# rtc_blk.net
KiCad netlist of a schematic drawn in Altium Designer
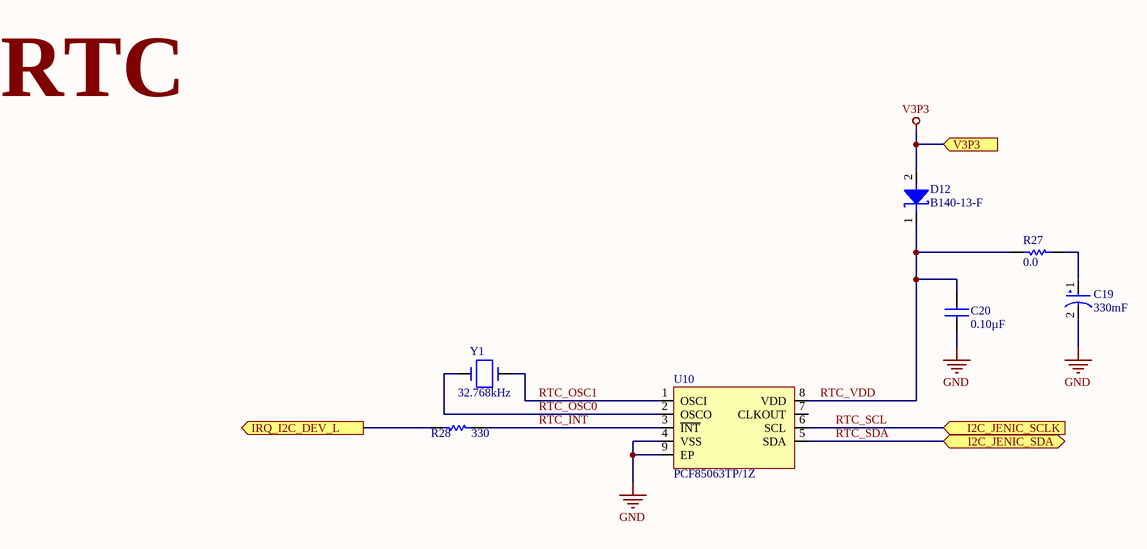
[diagram p0: rtc_blk.SchDoc]

(export (version "E")
  (design (tool "Eeschema 10.0.6"))
  (components
    (comp (ref "C19")
      (value "330mF")
      (footprint "ELNA_DSK-3R3H334T-HL")
      (description "CAP 330MF -20% +80% 3.3V SMD")
      (fields (field (name "MPN") "DSK-3R3H334T-HL"))
      (libsource (lib "Capacitor") (part "DSK-3R3H334T-HL"))
    )
    (comp (ref "C20")
      (value "0.10µF")
      (footprint "C0402")
      (description "CAP CER 0.1UF 50V X7R 0402")
      (fields (field (name "MPN") "GRM155R71H104ME14D"))
      (libsource (lib "Capacitor") (part "GRM155R71H104ME14D"))
    )
    (comp (ref "D12")
      (value "B140-13-F")
      (footprint "DO-214AC, SMA")
      (description "DIODE SCHOTTKY 40V 1A SMA")
      (libsource (lib "Diode") (part "B140-13-F"))
    )
    (comp (ref "R27")
      (value "0.0")
      (footprint "R0402")
      (description "RES SMD 0.0OHM JUMPER 1/16W 0402")
      (fields (field (name "MPN") "CRCW04020000Z0ED"))
      (libsource (lib "Res") (part "CRCW04020000Z0ED"))
    )
    (comp (ref "R28")
      (value "330")
      (footprint "R0402")
      (description "RES SMD 330 OHM 1% 1/16W 0402")
      (fields (field (name "MPN") "CRCW0402330RFKED"))
      (libsource (lib "Res") (part "CRCW0402330RFKED"))
    )
    (comp (ref "U10")
      (value "PCF85063TP/1Z")
      (footprint "SON9P50_200X300X80L40X24T150N")
      (description "Real Time Clock Serial 8-Pin HWSON EP")
      (fields (field (name "MPN") "PCF85063TP/1Z"))
      (libsource (lib "IC") (part "PCF85063TP/1Z"))
    )
    (comp (ref "Y1")
      (value "32.768kHz")
      (footprint "XTAL320X150X80L75X150N")
      (description "CRYSTAL 32.7680 KHZ 7.0PF SMD")
      (fields (field (name "MPN") "FC-13532.7680KA-AG5"))
      (libsource (lib "Crystal") (part "FC-13532.7680KA-AG5"))
    )
  )
  (nets
    (net (code "1") (name "/IRQ_I2C_DEV_L") (class "Default")
      (node (ref "R28") (pin "2") (pinfunction "2_2") (pintype "passive"))
    )
    (net (code "2") (name "/RTC_INT") (class "Default")
      (node (ref "R28") (pin "1") (pinfunction "1_1") (pintype "passive"))
      (node (ref "U10") (pin "3") (pinfunction "~{INT}_3") (pintype "passive"))
    )
    (net (code "3") (name "/RTC_OSC0") (class "Default")
      (node (ref "U10") (pin "2") (pinfunction "OSCO_2") (pintype "passive"))
      (node (ref "Y1") (pin "1") (pinfunction "1_1") (pintype "passive"))
    )
    (net (code "4") (name "/RTC_OSC1") (class "Default")
      (node (ref "U10") (pin "1") (pinfunction "OSCI_1") (pintype "passive"))
      (node (ref "Y1") (pin "2") (pinfunction "2_2") (pintype "passive"))
    )
    (net (code "5") (name "/RTC_SCL") (class "Default")
      (node (ref "U10") (pin "6") (pinfunction "SCL_6") (pintype "passive"))
    )
    (net (code "6") (name "/RTC_SDA") (class "Default")
      (node (ref "U10") (pin "5") (pinfunction "SDA_5") (pintype "passive"))
    )
    (net (code "7") (name "/RTC_VDD") (class "Default")
      (node (ref "C20") (pin "1") (pinfunction "1_1") (pintype "passive"))
      (node (ref "D12") (pin "1") (pinfunction "cathode_1") (pintype "passive"))
      (node (ref "R27") (pin "1") (pinfunction "1_1") (pintype "passive"))
      (node (ref "U10") (pin "8") (pinfunction "VDD_8") (pintype "passive"))
    )
    (net (code "8") (name "GND") (class "Default")
      (node (ref "C19") (pin "2") (pinfunction "2_2") (pintype "passive"))
      (node (ref "C20") (pin "2") (pinfunction "2_2") (pintype "passive"))
      (node (ref "U10") (pin "4") (pinfunction "VSS_4") (pintype "passive"))
      (node (ref "U10") (pin "9") (pinfunction "EP_9") (pintype "passive"))
    )
    (net (code "9") (name "Net-(C19-Pad1)") (class "Default")
      (node (ref "C19") (pin "1") (pinfunction "1_1") (pintype "passive"))
      (node (ref "R27") (pin "2") (pinfunction "2_2") (pintype "passive"))
    )
    (net (code "10") (name "V3P3") (class "Default")
      (node (ref "D12") (pin "2") (pinfunction "anode_2") (pintype "passive"))
    )
    (net (code "11") (name "unconnected-(U10-CLKOUT-Pad7)") (class "Default")
      (node (ref "U10") (pin "7") (pinfunction "CLKOUT_7") (pintype "passive"))
    )
  )
)
